# esquematico.net
KiCad netlist of a schematic drawn in EAGLE
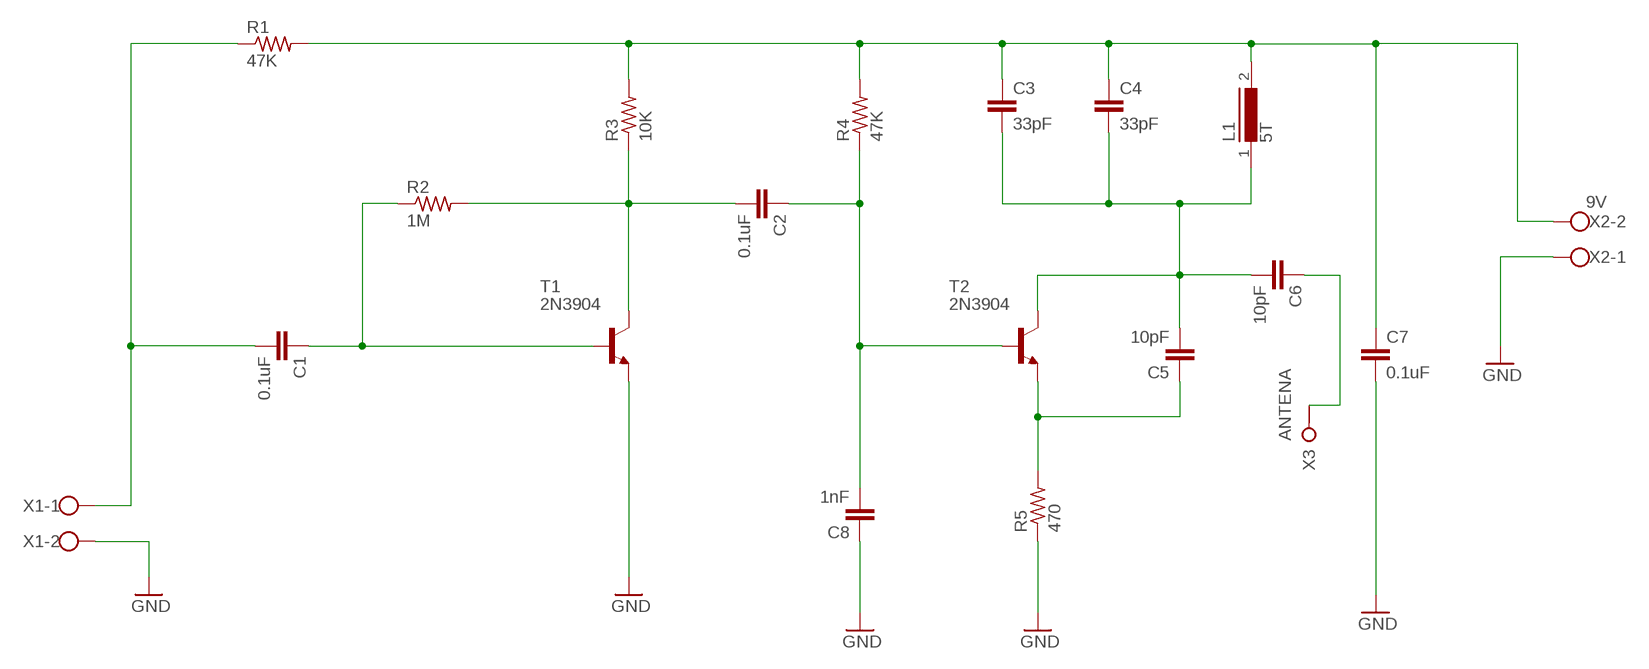
[diagram p0: schematic, sheet 1]

(export (version "E")
  (design (tool "Eeschema 10.0.6"))
  (components
    (comp (ref "C1")
      (value "0.1uF")
      (footprint "eagle-import:C025-025X050")
      (libsource (lib "eagle-import") (part "C-EU025-025X050"))
    )
    (comp (ref "C2")
      (value "0.1uF")
      (footprint "eagle-import:C025-025X050")
      (libsource (lib "eagle-import") (part "C-EU025-025X050"))
    )
    (comp (ref "C3")
      (value "33pF")
      (footprint "eagle-import:C025-025X050")
      (libsource (lib "eagle-import") (part "C-EU025-025X050"))
    )
    (comp (ref "C4")
      (value "33pF")
      (footprint "eagle-import:C025-025X050")
      (libsource (lib "eagle-import") (part "C-EU025-025X050"))
    )
    (comp (ref "C5")
      (value "10pF")
      (footprint "eagle-import:C025-025X050")
      (libsource (lib "eagle-import") (part "C-EU025-025X050"))
    )
    (comp (ref "C6")
      (value "10pF")
      (footprint "eagle-import:C025-025X050")
      (libsource (lib "eagle-import") (part "C-EU025-025X050"))
    )
    (comp (ref "C7")
      (value "0.1uF")
      (footprint "eagle-import:C025-025X050")
      (libsource (lib "eagle-import") (part "C-EU025-025X050"))
    )
    (comp (ref "C8")
      (value "1nF")
      (footprint "eagle-import:C025-025X050")
      (libsource (lib "eagle-import") (part "C-EU025-025X050"))
    )
    (comp (ref "L1")
      (value "5T")
      (footprint "eagle-import:A26GFC")
      (libsource (lib "eagle-import") (part "A26GFC"))
    )
    (comp (ref "R1")
      (value "47K")
      (footprint "eagle-import:0207_10")
      (libsource (lib "eagle-import") (part "R-US_0207/10"))
    )
    (comp (ref "R2")
      (value "1M")
      (footprint "eagle-import:0207_10")
      (libsource (lib "eagle-import") (part "R-US_0207/10"))
    )
    (comp (ref "R3")
      (value "10K")
      (footprint "eagle-import:0207_10")
      (libsource (lib "eagle-import") (part "R-US_0207/10"))
    )
    (comp (ref "R4")
      (value "47K")
      (footprint "eagle-import:0207_10")
      (libsource (lib "eagle-import") (part "R-US_0207/10"))
    )
    (comp (ref "R5")
      (value "470")
      (footprint "eagle-import:0207_10")
      (libsource (lib "eagle-import") (part "R-US_0207/10"))
    )
    (comp (ref "T1")
      (value "2N3904")
      (footprint "eagle-import:TO92")
      (libsource (lib "eagle-import") (part "2N3904"))
    )
    (comp (ref "T2")
      (value "2N3904")
      (footprint "eagle-import:TO92")
      (libsource (lib "eagle-import") (part "2N3904"))
    )
    (comp (ref "X1")
      (value "W237-102")
      (footprint "eagle-import:W237-102")
      (fields (field (name "MPN") "237-102"))
      (libsource (lib "eagle-import") (part "W237-102"))
    )
    (comp (ref "X2")
      (value "9V")
      (footprint "eagle-import:W237-102")
      (fields (field (name "MPN") "237-102"))
      (libsource (lib "eagle-import") (part "W237-102"))
    )
    (comp (ref "X3")
      (value "ANTENA")
      (footprint "eagle-import:W236-1")
      (libsource (lib "eagle-import") (part "W236-1"))
    )
  )
  (nets
    (net (code "1") (name "GND") (class "Default")
      (node (ref "C7") (pin "2") (pinfunction "2_2") (pintype "passive"))
      (node (ref "C8") (pin "1") (pinfunction "1_1") (pintype "passive"))
      (node (ref "R5") (pin "1") (pinfunction "1_1") (pintype "passive"))
      (node (ref "T1") (pin "3") (pinfunction "E_3") (pintype "passive"))
      (node (ref "X1") (pin "2") (pinfunction "KL_2") (pintype "passive"))
      (node (ref "X2") (pin "1") (pinfunction "KL_1") (pintype "passive"))
    )
    (net (code "2") (name "Net-(T1-B)") (class "Default")
      (node (ref "C1") (pin "1") (pinfunction "1_1") (pintype "passive"))
      (node (ref "R2") (pin "1") (pinfunction "1_1") (pintype "passive"))
      (node (ref "T1") (pin "2") (pinfunction "B_2") (pintype "passive"))
    )
    (net (code "3") (name "Net-(T1-C)") (class "Default")
      (node (ref "C2") (pin "2") (pinfunction "2_2") (pintype "passive"))
      (node (ref "R2") (pin "2") (pinfunction "2_2") (pintype "passive"))
      (node (ref "R3") (pin "1") (pinfunction "1_1") (pintype "passive"))
      (node (ref "T1") (pin "1") (pinfunction "C_1") (pintype "passive"))
    )
    (net (code "4") (name "Net-(T2-B)") (class "Default")
      (node (ref "C2") (pin "1") (pinfunction "1_1") (pintype "passive"))
      (node (ref "C8") (pin "2") (pinfunction "2_2") (pintype "passive"))
      (node (ref "R4") (pin "1") (pinfunction "1_1") (pintype "passive"))
      (node (ref "T2") (pin "2") (pinfunction "B_2") (pintype "passive"))
    )
    (net (code "5") (name "Net-(T2-C)") (class "Default")
      (node (ref "C3") (pin "2") (pinfunction "2_2") (pintype "passive"))
      (node (ref "C4") (pin "2") (pinfunction "2_2") (pintype "passive"))
      (node (ref "C5") (pin "2") (pinfunction "2_2") (pintype "passive"))
      (node (ref "C6") (pin "2") (pinfunction "2_2") (pintype "passive"))
      (node (ref "L1") (pin "1") (pinfunction "1_1") (pintype "passive"))
      (node (ref "T2") (pin "1") (pinfunction "C_1") (pintype "passive"))
    )
    (net (code "6") (name "Net-(T2-E)") (class "Default")
      (node (ref "C5") (pin "1") (pinfunction "1_1") (pintype "passive"))
      (node (ref "R5") (pin "2") (pinfunction "2_2") (pintype "passive"))
      (node (ref "T2") (pin "3") (pinfunction "E_3") (pintype "passive"))
    )
    (net (code "7") (name "Net-(X1A-KL)") (class "Default")
      (node (ref "C1") (pin "2") (pinfunction "2_2") (pintype "passive"))
      (node (ref "R1") (pin "1") (pinfunction "1_1") (pintype "passive"))
      (node (ref "X1") (pin "1") (pinfunction "KL_1") (pintype "passive"))
    )
    (net (code "8") (name "Net-(X2B-KL)") (class "Default")
      (node (ref "C3") (pin "1") (pinfunction "1_1") (pintype "passive"))
      (node (ref "C4") (pin "1") (pinfunction "1_1") (pintype "passive"))
      (node (ref "C7") (pin "1") (pinfunction "1_1") (pintype "passive"))
      (node (ref "L1") (pin "2") (pinfunction "2_2") (pintype "passive"))
      (node (ref "R1") (pin "2") (pinfunction "2_2") (pintype "passive"))
      (node (ref "R3") (pin "2") (pinfunction "2_2") (pintype "passive"))
      (node (ref "R4") (pin "2") (pinfunction "2_2") (pintype "passive"))
      (node (ref "X2") (pin "2") (pinfunction "KL_2") (pintype "passive"))
    )
    (net (code "9") (name "Net-(X3-KL1)") (class "Default")
      (node (ref "C6") (pin "1") (pinfunction "1_1") (pintype "passive"))
      (node (ref "X3") (pin "1") (pinfunction "KL1_1") (pintype "passive"))
    )
    (net (code "10") (name "unconnected-(X3-KL2-Pad2)") (class "Default")
      (node (ref "X3") (pin "2") (pinfunction "KL2_2") (pintype "passive"))
    )
  )
)
